# pardisplay.net
KiCad netlist of a schematic drawn in EAGLE
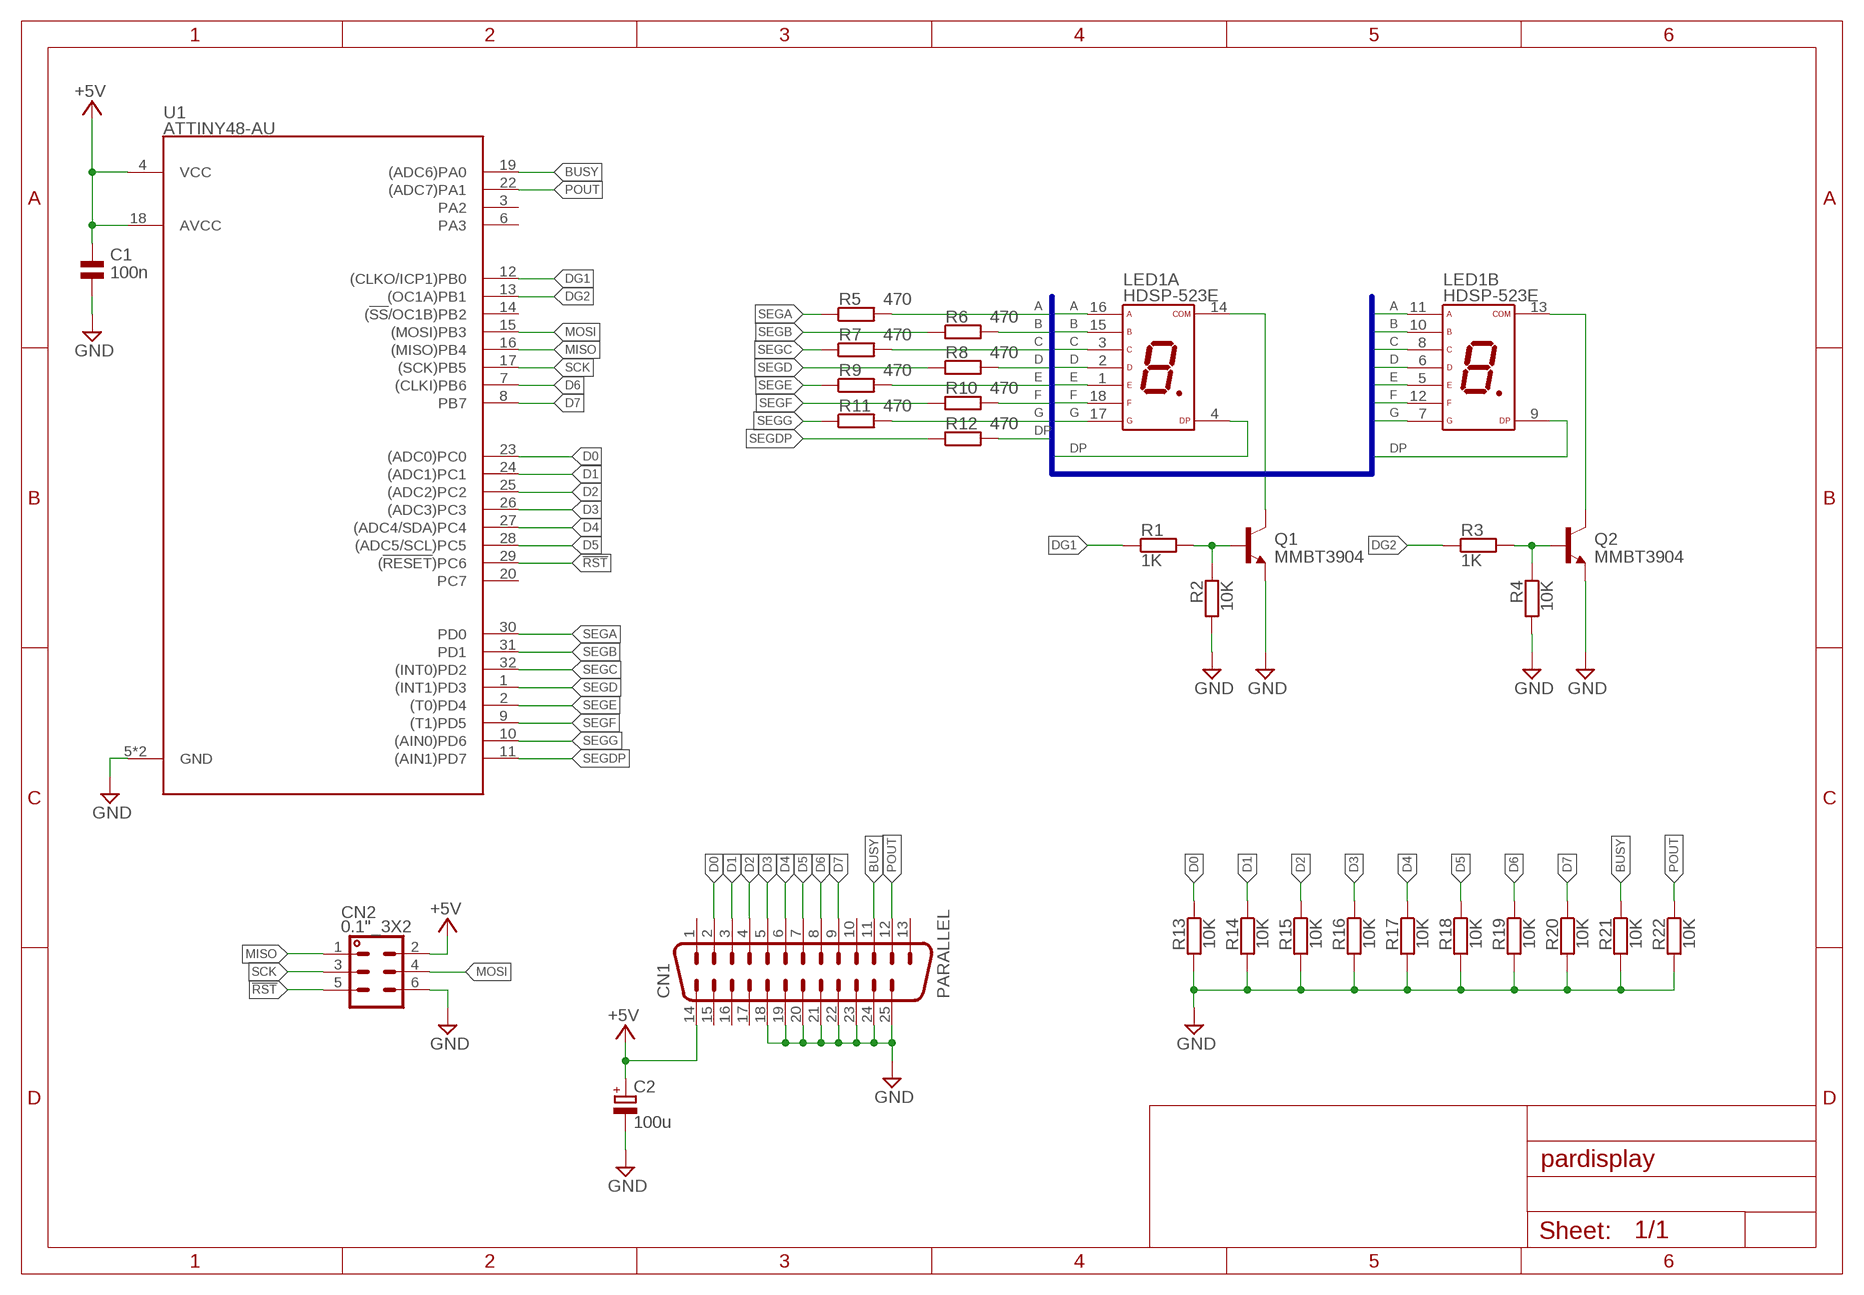
[diagram p0: schematic, sheet 1]

(export (version "E")
  (design (tool "Eeschema 10.0.6"))
  (components
    (comp (ref "C1")
      (value "100n")
      (footprint "eagle-import:0603")
      (libsource (lib "eagle-import") (part "CAP_NPOL0603-"))
    )
    (comp (ref "C2")
      (value "100u")
      (footprint "eagle-import:UD-6,3X5,8_NICHICON")
      (libsource (lib "eagle-import") (part "CPOL-EUUD-6,3X8,8"))
    )
    (comp (ref "CN1")
      (value "PARALLEL")
      (footprint "eagle-import:M25HP")
      (libsource (lib "eagle-import") (part "M25HP"))
    )
    (comp (ref "CN2")
      (value "0.1\"_3X2")
      (footprint "eagle-import:0.1__3X2-LONG")
      (libsource (lib "eagle-import") (part "0.1{dblquote}_3X2"))
    )
    (comp (ref "LED1")
      (value "HDSP-523E")
      (footprint "eagle-import:DA56")
      (libsource (lib "eagle-import") (part "KINGBRIGHT_DA56"))
    )
    (comp (ref "Q1")
      (value "MMBT3904")
      (footprint "eagle-import:SOT23")
      (libsource (lib "eagle-import") (part "-NPN_?SOT23"))
    )
    (comp (ref "Q2")
      (value "MMBT3904")
      (footprint "eagle-import:SOT23")
      (libsource (lib "eagle-import") (part "-NPN_?SOT23"))
    )
    (comp (ref "R1")
      (value "1K")
      (footprint "eagle-import:0603")
      (libsource (lib "eagle-import") (part "RESSMD_0603-"))
    )
    (comp (ref "R2")
      (value "10K")
      (footprint "eagle-import:0603")
      (libsource (lib "eagle-import") (part "RESSMD_0603-"))
    )
    (comp (ref "R3")
      (value "1K")
      (footprint "eagle-import:0603")
      (libsource (lib "eagle-import") (part "RESSMD_0603-"))
    )
    (comp (ref "R4")
      (value "10K")
      (footprint "eagle-import:0603")
      (libsource (lib "eagle-import") (part "RESSMD_0603-"))
    )
    (comp (ref "R5")
      (value "470")
      (footprint "eagle-import:0603")
      (libsource (lib "eagle-import") (part "RESSMD_0603-"))
    )
    (comp (ref "R6")
      (value "470")
      (footprint "eagle-import:0603")
      (libsource (lib "eagle-import") (part "RESSMD_0603-"))
    )
    (comp (ref "R7")
      (value "470")
      (footprint "eagle-import:0603")
      (libsource (lib "eagle-import") (part "RESSMD_0603-"))
    )
    (comp (ref "R8")
      (value "470")
      (footprint "eagle-import:0603")
      (libsource (lib "eagle-import") (part "RESSMD_0603-"))
    )
    (comp (ref "R9")
      (value "470")
      (footprint "eagle-import:0603")
      (libsource (lib "eagle-import") (part "RESSMD_0603-"))
    )
    (comp (ref "R10")
      (value "470")
      (footprint "eagle-import:0603")
      (libsource (lib "eagle-import") (part "RESSMD_0603-"))
    )
    (comp (ref "R11")
      (value "470")
      (footprint "eagle-import:0603")
      (libsource (lib "eagle-import") (part "RESSMD_0603-"))
    )
    (comp (ref "R12")
      (value "470")
      (footprint "eagle-import:0603")
      (libsource (lib "eagle-import") (part "RESSMD_0603-"))
    )
    (comp (ref "R13")
      (value "10K")
      (footprint "eagle-import:0603")
      (libsource (lib "eagle-import") (part "RESSMD_0603-"))
    )
    (comp (ref "R14")
      (value "10K")
      (footprint "eagle-import:0603")
      (libsource (lib "eagle-import") (part "RESSMD_0603-"))
    )
    (comp (ref "R15")
      (value "10K")
      (footprint "eagle-import:0603")
      (libsource (lib "eagle-import") (part "RESSMD_0603-"))
    )
    (comp (ref "R16")
      (value "10K")
      (footprint "eagle-import:0603")
      (libsource (lib "eagle-import") (part "RESSMD_0603-"))
    )
    (comp (ref "R17")
      (value "10K")
      (footprint "eagle-import:0603")
      (libsource (lib "eagle-import") (part "RESSMD_0603-"))
    )
    (comp (ref "R18")
      (value "10K")
      (footprint "eagle-import:0603")
      (libsource (lib "eagle-import") (part "RESSMD_0603-"))
    )
    (comp (ref "R19")
      (value "10K")
      (footprint "eagle-import:0603")
      (libsource (lib "eagle-import") (part "RESSMD_0603-"))
    )
    (comp (ref "R20")
      (value "10K")
      (footprint "eagle-import:0603")
      (libsource (lib "eagle-import") (part "RESSMD_0603-"))
    )
    (comp (ref "R21")
      (value "10K")
      (footprint "eagle-import:0603")
      (libsource (lib "eagle-import") (part "RESSMD_0603-"))
    )
    (comp (ref "R22")
      (value "10K")
      (footprint "eagle-import:0603")
      (libsource (lib "eagle-import") (part "RESSMD_0603-"))
    )
    (comp (ref "U1")
      (value "ATTINY48-AU")
      (footprint "eagle-import:TQFP32-08")
      (libsource (lib "eagle-import") (part "ATTINY8-AU4"))
    )
  )
  (nets
    (net (code "1") (name "+5V") (class "Default")
      (node (ref "C1") (pin "1") (pinfunction "1_1") (pintype "passive"))
      (node (ref "C2") (pin "+") (pinfunction "+_+") (pintype "passive"))
      (node (ref "CN1") (pin "14") (pinfunction "14_14") (pintype "passive"))
      (node (ref "CN2") (pin "2") (pinfunction "2_2") (pintype "passive"))
      (node (ref "U1") (pin "18") (pinfunction "AVCC_18") (pintype "power_in"))
      (node (ref "U1") (pin "4") (pinfunction "VCC_4") (pintype "power_in"))
    )
    (net (code "2") (name "/A") (class "Default")
      (node (ref "LED1") (pin "11") (pinfunction "A_11") (pintype "passive"))
      (node (ref "LED1") (pin "16") (pinfunction "A_16") (pintype "passive"))
      (node (ref "R5") (pin "2") (pinfunction "2_2") (pintype "passive"))
    )
    (net (code "3") (name "/B") (class "Default")
      (node (ref "LED1") (pin "10") (pinfunction "B_10") (pintype "passive"))
      (node (ref "LED1") (pin "15") (pinfunction "B_15") (pintype "passive"))
      (node (ref "R6") (pin "2") (pinfunction "2_2") (pintype "passive"))
    )
    (net (code "4") (name "/C") (class "Default")
      (node (ref "LED1") (pin "3") (pinfunction "C_3") (pintype "passive"))
      (node (ref "LED1") (pin "8") (pinfunction "C_8") (pintype "passive"))
      (node (ref "R7") (pin "2") (pinfunction "2_2") (pintype "passive"))
    )
    (net (code "5") (name "/D") (class "Default")
      (node (ref "LED1") (pin "2") (pinfunction "D_2") (pintype "passive"))
      (node (ref "LED1") (pin "6") (pinfunction "D_6") (pintype "passive"))
      (node (ref "R8") (pin "2") (pinfunction "2_2") (pintype "passive"))
    )
    (net (code "6") (name "/DP") (class "Default")
      (node (ref "LED1") (pin "4") (pinfunction "DP_4") (pintype "passive"))
      (node (ref "LED1") (pin "9") (pinfunction "DP_9") (pintype "passive"))
      (node (ref "R12") (pin "2") (pinfunction "2_2") (pintype "passive"))
    )
    (net (code "7") (name "/E") (class "Default")
      (node (ref "LED1") (pin "1") (pinfunction "E_1") (pintype "passive"))
      (node (ref "LED1") (pin "5") (pinfunction "E_5") (pintype "passive"))
      (node (ref "R9") (pin "2") (pinfunction "2_2") (pintype "passive"))
    )
    (net (code "8") (name "/F") (class "Default")
      (node (ref "LED1") (pin "12") (pinfunction "F_12") (pintype "passive"))
      (node (ref "LED1") (pin "18") (pinfunction "F_18") (pintype "passive"))
      (node (ref "R10") (pin "2") (pinfunction "2_2") (pintype "passive"))
    )
    (net (code "9") (name "/G") (class "Default")
      (node (ref "LED1") (pin "17") (pinfunction "G_17") (pintype "passive"))
      (node (ref "LED1") (pin "7") (pinfunction "G_7") (pintype "passive"))
      (node (ref "R11") (pin "2") (pinfunction "2_2") (pintype "passive"))
    )
    (net (code "10") (name "/~{RST}") (class "Default")
      (node (ref "CN2") (pin "5") (pinfunction "5_5") (pintype "passive"))
      (node (ref "U1") (pin "29") (pinfunction "(~{RESET})PC6_29") (pintype "passive"))
    )
    (net (code "11") (name "BUSY") (class "Default")
      (node (ref "CN1") (pin "11") (pinfunction "11_11") (pintype "passive"))
      (node (ref "R21") (pin "1") (pinfunction "1_1") (pintype "passive"))
      (node (ref "U1") (pin "19") (pinfunction "(ADC6)PA0_19") (pintype "passive"))
    )
    (net (code "12") (name "D0") (class "Default")
      (node (ref "CN1") (pin "2") (pinfunction "2_2") (pintype "passive"))
      (node (ref "R13") (pin "1") (pinfunction "1_1") (pintype "passive"))
      (node (ref "U1") (pin "23") (pinfunction "(ADC0)PC0_23") (pintype "passive"))
    )
    (net (code "13") (name "D1") (class "Default")
      (node (ref "CN1") (pin "3") (pinfunction "3_3") (pintype "passive"))
      (node (ref "R14") (pin "1") (pinfunction "1_1") (pintype "passive"))
      (node (ref "U1") (pin "24") (pinfunction "(ADC1)PC1_24") (pintype "passive"))
    )
    (net (code "14") (name "D2") (class "Default")
      (node (ref "CN1") (pin "4") (pinfunction "4_4") (pintype "passive"))
      (node (ref "R15") (pin "1") (pinfunction "1_1") (pintype "passive"))
      (node (ref "U1") (pin "25") (pinfunction "(ADC2)PC2_25") (pintype "passive"))
    )
    (net (code "15") (name "D3") (class "Default")
      (node (ref "CN1") (pin "5") (pinfunction "5_5") (pintype "passive"))
      (node (ref "R16") (pin "1") (pinfunction "1_1") (pintype "passive"))
      (node (ref "U1") (pin "26") (pinfunction "(ADC3)PC3_26") (pintype "passive"))
    )
    (net (code "16") (name "D4") (class "Default")
      (node (ref "CN1") (pin "6") (pinfunction "6_6") (pintype "passive"))
      (node (ref "R17") (pin "1") (pinfunction "1_1") (pintype "passive"))
      (node (ref "U1") (pin "27") (pinfunction "(ADC4/SDA)PC4_27") (pintype "passive"))
    )
    (net (code "17") (name "D5") (class "Default")
      (node (ref "CN1") (pin "7") (pinfunction "7_7") (pintype "passive"))
      (node (ref "R18") (pin "1") (pinfunction "1_1") (pintype "passive"))
      (node (ref "U1") (pin "28") (pinfunction "(ADC5/SCL)PC5_28") (pintype "passive"))
    )
    (net (code "18") (name "D6") (class "Default")
      (node (ref "CN1") (pin "8") (pinfunction "8_8") (pintype "passive"))
      (node (ref "R19") (pin "1") (pinfunction "1_1") (pintype "passive"))
      (node (ref "U1") (pin "7") (pinfunction "(CLKI)PB6_7") (pintype "passive"))
    )
    (net (code "19") (name "D7") (class "Default")
      (node (ref "CN1") (pin "9") (pinfunction "9_9") (pintype "passive"))
      (node (ref "R20") (pin "1") (pinfunction "1_1") (pintype "passive"))
      (node (ref "U1") (pin "8") (pinfunction "PB7_8") (pintype "passive"))
    )
    (net (code "20") (name "DG1") (class "Default")
      (node (ref "R1") (pin "1") (pinfunction "1_1") (pintype "passive"))
      (node (ref "U1") (pin "12") (pinfunction "(CLKO/ICP1)PB0_12") (pintype "passive"))
    )
    (net (code "21") (name "DG2") (class "Default")
      (node (ref "R3") (pin "1") (pinfunction "1_1") (pintype "passive"))
      (node (ref "U1") (pin "13") (pinfunction "(OC1A)PB1_13") (pintype "passive"))
    )
    (net (code "22") (name "GND") (class "Default")
      (node (ref "C1") (pin "2") (pinfunction "2_2") (pintype "passive"))
      (node (ref "C2") (pin "-") (pinfunction "-_-") (pintype "passive"))
      (node (ref "CN1") (pin "18") (pinfunction "18_18") (pintype "passive"))
      (node (ref "CN1") (pin "19") (pinfunction "19_19") (pintype "passive"))
      (node (ref "CN1") (pin "20") (pinfunction "20_20") (pintype "passive"))
      (node (ref "CN1") (pin "21") (pinfunction "21_21") (pintype "passive"))
      (node (ref "CN1") (pin "22") (pinfunction "22_22") (pintype "passive"))
      (node (ref "CN1") (pin "23") (pinfunction "23_23") (pintype "passive"))
      (node (ref "CN1") (pin "24") (pinfunction "24_24") (pintype "passive"))
      (node (ref "CN1") (pin "25") (pinfunction "25_25") (pintype "passive"))
      (node (ref "CN2") (pin "6") (pinfunction "6_6") (pintype "passive"))
      (node (ref "Q1") (pin "2") (pinfunction "E_2") (pintype "passive"))
      (node (ref "Q2") (pin "2") (pinfunction "E_2") (pintype "passive"))
      (node (ref "R13") (pin "2") (pinfunction "2_2") (pintype "passive"))
      (node (ref "R14") (pin "2") (pinfunction "2_2") (pintype "passive"))
      (node (ref "R15") (pin "2") (pinfunction "2_2") (pintype "passive"))
      (node (ref "R16") (pin "2") (pinfunction "2_2") (pintype "passive"))
      (node (ref "R17") (pin "2") (pinfunction "2_2") (pintype "passive"))
      (node (ref "R18") (pin "2") (pinfunction "2_2") (pintype "passive"))
      (node (ref "R19") (pin "2") (pinfunction "2_2") (pintype "passive"))
      (node (ref "R2") (pin "2") (pinfunction "2_2") (pintype "passive"))
      (node (ref "R20") (pin "2") (pinfunction "2_2") (pintype "passive"))
      (node (ref "R21") (pin "2") (pinfunction "2_2") (pintype "passive"))
      (node (ref "R22") (pin "2") (pinfunction "2_2") (pintype "passive"))
      (node (ref "R4") (pin "2") (pinfunction "2_2") (pintype "passive"))
      (node (ref "U1") (pin "21") (pinfunction "GND_21") (pintype "power_in"))
      (node (ref "U1") (pin "5") (pinfunction "GND_5") (pintype "power_in"))
    )
    (net (code "23") (name "MISO") (class "Default")
      (node (ref "CN2") (pin "1") (pinfunction "1_1") (pintype "passive"))
      (node (ref "U1") (pin "16") (pinfunction "(MISO)PB4_16") (pintype "passive"))
    )
    (net (code "24") (name "MOSI") (class "Default")
      (node (ref "CN2") (pin "4") (pinfunction "4_4") (pintype "passive"))
      (node (ref "U1") (pin "15") (pinfunction "(MOSI)PB3_15") (pintype "passive"))
    )
    (net (code "25") (name "Net-(LED1A-COM)") (class "Default")
      (node (ref "LED1") (pin "14") (pinfunction "COM_14") (pintype "passive"))
      (node (ref "Q1") (pin "3") (pinfunction "C_3") (pintype "passive"))
    )
    (net (code "26") (name "Net-(LED1B-COM)") (class "Default")
      (node (ref "LED1") (pin "13") (pinfunction "COM_13") (pintype "passive"))
      (node (ref "Q2") (pin "3") (pinfunction "C_3") (pintype "passive"))
    )
    (net (code "27") (name "Net-(Q1-B)") (class "Default")
      (node (ref "Q1") (pin "1") (pinfunction "B_1") (pintype "passive"))
      (node (ref "R1") (pin "2") (pinfunction "2_2") (pintype "passive"))
      (node (ref "R2") (pin "1") (pinfunction "1_1") (pintype "passive"))
    )
    (net (code "28") (name "Net-(Q2-B)") (class "Default")
      (node (ref "Q2") (pin "1") (pinfunction "B_1") (pintype "passive"))
      (node (ref "R3") (pin "2") (pinfunction "2_2") (pintype "passive"))
      (node (ref "R4") (pin "1") (pinfunction "1_1") (pintype "passive"))
    )
    (net (code "29") (name "POUT") (class "Default")
      (node (ref "CN1") (pin "12") (pinfunction "12_12") (pintype "passive"))
      (node (ref "R22") (pin "1") (pinfunction "1_1") (pintype "passive"))
      (node (ref "U1") (pin "22") (pinfunction "(ADC7)PA1_22") (pintype "passive"))
    )
    (net (code "30") (name "SCK") (class "Default")
      (node (ref "CN2") (pin "3") (pinfunction "3_3") (pintype "passive"))
      (node (ref "U1") (pin "17") (pinfunction "(SCK)PB5_17") (pintype "passive"))
    )
    (net (code "31") (name "SEGA") (class "Default")
      (node (ref "R5") (pin "1") (pinfunction "1_1") (pintype "passive"))
      (node (ref "U1") (pin "30") (pinfunction "PD0_30") (pintype "passive"))
    )
    (net (code "32") (name "SEGB") (class "Default")
      (node (ref "R6") (pin "1") (pinfunction "1_1") (pintype "passive"))
      (node (ref "U1") (pin "31") (pinfunction "PD1_31") (pintype "passive"))
    )
    (net (code "33") (name "SEGC") (class "Default")
      (node (ref "R7") (pin "1") (pinfunction "1_1") (pintype "passive"))
      (node (ref "U1") (pin "32") (pinfunction "(INT0)PD2_32") (pintype "passive"))
    )
    (net (code "34") (name "SEGD") (class "Default")
      (node (ref "R8") (pin "1") (pinfunction "1_1") (pintype "passive"))
      (node (ref "U1") (pin "1") (pinfunction "(INT1)PD3_1") (pintype "passive"))
    )
    (net (code "35") (name "SEGDP") (class "Default")
      (node (ref "R12") (pin "1") (pinfunction "1_1") (pintype "passive"))
      (node (ref "U1") (pin "11") (pinfunction "(AIN1)PD7_11") (pintype "passive"))
    )
    (net (code "36") (name "SEGE") (class "Default")
      (node (ref "R9") (pin "1") (pinfunction "1_1") (pintype "passive"))
      (node (ref "U1") (pin "2") (pinfunction "(T0)PD4_2") (pintype "passive"))
    )
    (net (code "37") (name "SEGF") (class "Default")
      (node (ref "R10") (pin "1") (pinfunction "1_1") (pintype "passive"))
      (node (ref "U1") (pin "9") (pinfunction "(T1)PD5_9") (pintype "passive"))
    )
    (net (code "38") (name "SEGG") (class "Default")
      (node (ref "R11") (pin "1") (pinfunction "1_1") (pintype "passive"))
      (node (ref "U1") (pin "10") (pinfunction "(AIN0)PD6_10") (pintype "passive"))
    )
    (net (code "39") (name "unconnected-(CN1-Pad1)") (class "Default")
      (node (ref "CN1") (pin "1") (pinfunction "1_1") (pintype "passive"))
    )
    (net (code "40") (name "unconnected-(CN1-Pad10)") (class "Default")
      (node (ref "CN1") (pin "10") (pinfunction "10_10") (pintype "passive"))
    )
    (net (code "41") (name "unconnected-(CN1-Pad13)") (class "Default")
      (node (ref "CN1") (pin "13") (pinfunction "13_13") (pintype "passive"))
    )
    (net (code "42") (name "unconnected-(CN1-Pad15)") (class "Default")
      (node (ref "CN1") (pin "15") (pinfunction "15_15") (pintype "passive"))
    )
    (net (code "43") (name "unconnected-(CN1-Pad16)") (class "Default")
      (node (ref "CN1") (pin "16") (pinfunction "16_16") (pintype "passive"))
    )
    (net (code "44") (name "unconnected-(CN1-Pad17)") (class "Default")
      (node (ref "CN1") (pin "17") (pinfunction "17_17") (pintype "passive"))
    )
    (net (code "45") (name "unconnected-(U1-(~{SS}{slash}OC1B)PB2-Pad14)") (class "Default")
      (node (ref "U1") (pin "14") (pinfunction "(~{SS}/OC1B)PB2_14") (pintype "passive"))
    )
    (net (code "46") (name "unconnected-(U1-PA2-Pad3)") (class "Default")
      (node (ref "U1") (pin "3") (pinfunction "PA2_3") (pintype "passive"))
    )
    (net (code "47") (name "unconnected-(U1-PA3-Pad6)") (class "Default")
      (node (ref "U1") (pin "6") (pinfunction "PA3_6") (pintype "passive"))
    )
    (net (code "48") (name "unconnected-(U1-PC7-Pad20)") (class "Default")
      (node (ref "U1") (pin "20") (pinfunction "PC7_20") (pintype "passive"))
    )
  )
)
